# cloud_sensor.net
KiCad netlist of a schematic drawn in EAGLE
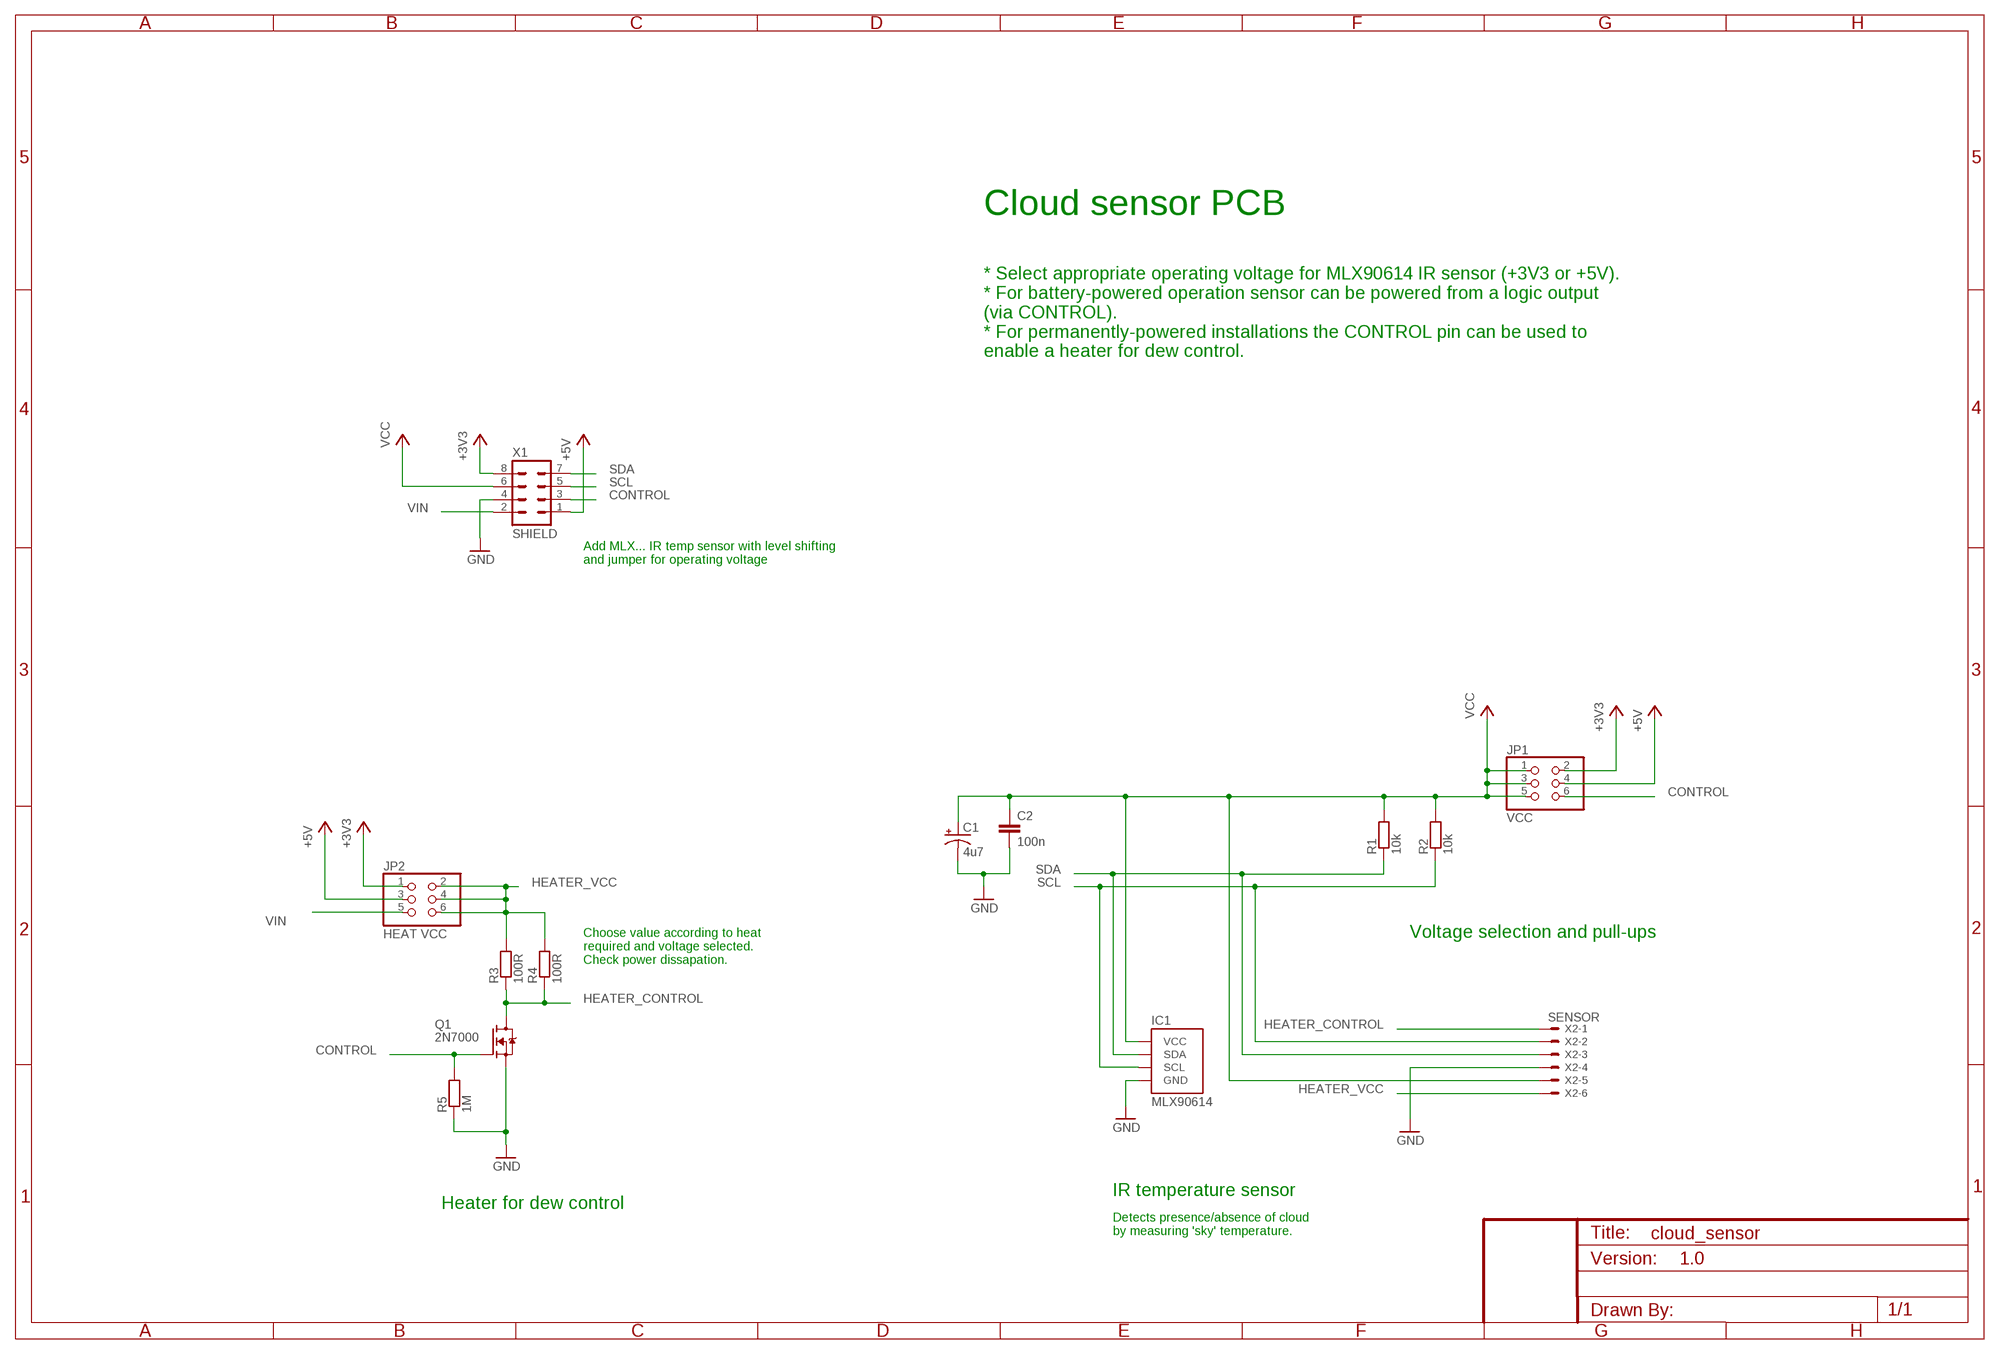
[diagram p0: schematic, sheet 1]

(export (version "E")
  (design (tool "Eeschema 10.0.6"))
  (components
    (comp (ref "C1")
      (value "4u7")
      (footprint "eagle-import:CPOL-RADIAL-10UF-25V")
      (libsource (lib "eagle-import") (part "CAP_POLPTH2"))
    )
    (comp (ref "C2")
      (value "100n")
      (footprint "eagle-import:CAP-PTH-SMALL")
      (libsource (lib "eagle-import") (part "CAPPTH"))
    )
    (comp (ref "IC1")
      (value "MLX90614")
      (footprint "eagle-import:TO39-4")
      (libsource (lib "eagle-import") (part "MLX90614TO-39"))
    )
    (comp (ref "JP1")
      (value "VCC")
      (footprint "eagle-import:2X03")
      (libsource (lib "eagle-import") (part "PINHD-2X3"))
    )
    (comp (ref "JP2")
      (value "HEAT VCC")
      (footprint "eagle-import:2X03")
      (libsource (lib "eagle-import") (part "PINHD-2X3"))
    )
    (comp (ref "Q1")
      (value "2N7000")
      (footprint "eagle-import:TO-92")
      (libsource (lib "eagle-import") (part "2N7000"))
    )
    (comp (ref "R1")
      (value "10k")
      (footprint "eagle-import:RES-AXIAL-0.4")
      (libsource (lib "eagle-import") (part "RESISTOR"))
    )
    (comp (ref "R2")
      (value "10k")
      (footprint "eagle-import:RES-AXIAL-0.4")
      (libsource (lib "eagle-import") (part "RESISTOR"))
    )
    (comp (ref "R3")
      (value "100R")
      (footprint "eagle-import:RES-AXIAL-0.4")
      (libsource (lib "eagle-import") (part "RESISTOR"))
    )
    (comp (ref "R4")
      (value "100R")
      (footprint "eagle-import:RES-AXIAL-0.4")
      (libsource (lib "eagle-import") (part "RESISTOR"))
    )
    (comp (ref "R5")
      (value "1M")
      (footprint "eagle-import:RES-AXIAL-0.4")
      (libsource (lib "eagle-import") (part "RESISTOR"))
    )
    (comp (ref "X1")
      (value "SHIELD")
      (footprint "eagle-import:ML8")
      (libsource (lib "eagle-import") (part "ML8"))
    )
    (comp (ref "X2")
      (value "SENSOR")
      (footprint "eagle-import:22-23-2061")
      (fields (field (name "MF") "MOLEX") (field (name "MPN") "22-23-2061"))
      (libsource (lib "eagle-import") (part "22-23-2061"))
    )
  )
  (nets
    (net (code "1") (name "+3V3") (class "Default")
      (node (ref "JP1") (pin "2") (pinfunction "2_2") (pintype "passive"))
      (node (ref "JP2") (pin "1") (pinfunction "1_1") (pintype "passive"))
      (node (ref "X1") (pin "8") (pinfunction "8_8") (pintype "passive"))
    )
    (net (code "2") (name "+5V") (class "Default")
      (node (ref "JP1") (pin "4") (pinfunction "4_4") (pintype "passive"))
      (node (ref "JP2") (pin "3") (pinfunction "3_3") (pintype "passive"))
      (node (ref "X1") (pin "1") (pinfunction "1_1") (pintype "passive"))
    )
    (net (code "3") (name "/CONTROL") (class "Default")
      (node (ref "JP1") (pin "6") (pinfunction "6_6") (pintype "passive"))
      (node (ref "Q1") (pin "2") (pinfunction "G_2") (pintype "passive"))
      (node (ref "R5") (pin "P$2") (pinfunction "2_P$2") (pintype "passive"))
      (node (ref "X1") (pin "3") (pinfunction "3_3") (pintype "passive"))
    )
    (net (code "4") (name "/HEATER_CONTROL") (class "Default")
      (node (ref "Q1") (pin "3") (pinfunction "D_3") (pintype "passive"))
      (node (ref "R3") (pin "P$1") (pinfunction "1_P$1") (pintype "passive"))
      (node (ref "R4") (pin "P$1") (pinfunction "1_P$1") (pintype "passive"))
      (node (ref "X2") (pin "1") (pinfunction "S_1") (pintype "passive"))
    )
    (net (code "5") (name "/HEATER_VCC") (class "Default")
      (node (ref "JP2") (pin "2") (pinfunction "2_2") (pintype "passive"))
      (node (ref "JP2") (pin "4") (pinfunction "4_4") (pintype "passive"))
      (node (ref "JP2") (pin "6") (pinfunction "6_6") (pintype "passive"))
      (node (ref "R3") (pin "P$2") (pinfunction "2_P$2") (pintype "passive"))
      (node (ref "R4") (pin "P$2") (pinfunction "2_P$2") (pintype "passive"))
      (node (ref "X2") (pin "6") (pinfunction "S_6") (pintype "passive"))
    )
    (net (code "6") (name "/SCL") (class "Default")
      (node (ref "IC1") (pin "1") (pinfunction "SCL_1") (pintype "bidirectional"))
      (node (ref "R2") (pin "P$1") (pinfunction "1_P$1") (pintype "passive"))
      (node (ref "X1") (pin "5") (pinfunction "5_5") (pintype "passive"))
      (node (ref "X2") (pin "2") (pinfunction "S_2") (pintype "passive"))
    )
    (net (code "7") (name "/SDA") (class "Default")
      (node (ref "IC1") (pin "2") (pinfunction "SDA_2") (pintype "bidirectional"))
      (node (ref "R1") (pin "P$1") (pinfunction "1_P$1") (pintype "passive"))
      (node (ref "X1") (pin "7") (pinfunction "7_7") (pintype "passive"))
      (node (ref "X2") (pin "3") (pinfunction "S_3") (pintype "passive"))
    )
    (net (code "8") (name "/VIN") (class "Default")
      (node (ref "JP2") (pin "5") (pinfunction "5_5") (pintype "passive"))
      (node (ref "X1") (pin "2") (pinfunction "2_2") (pintype "passive"))
    )
    (net (code "9") (name "GND") (class "Default")
      (node (ref "C1") (pin "2") (pinfunction "-_2") (pintype "passive"))
      (node (ref "C2") (pin "2") (pinfunction "2_2") (pintype "passive"))
      (node (ref "IC1") (pin "4") (pinfunction "GND_4") (pintype "power_in"))
      (node (ref "Q1") (pin "1") (pinfunction "S_1") (pintype "passive"))
      (node (ref "R5") (pin "P$1") (pinfunction "1_P$1") (pintype "passive"))
      (node (ref "X1") (pin "4") (pinfunction "4_4") (pintype "passive"))
      (node (ref "X2") (pin "4") (pinfunction "S_4") (pintype "passive"))
    )
    (net (code "10") (name "VCC") (class "Default")
      (node (ref "C1") (pin "1") (pinfunction "+_1") (pintype "passive"))
      (node (ref "C2") (pin "1") (pinfunction "1_1") (pintype "passive"))
      (node (ref "IC1") (pin "3") (pinfunction "VCC_3") (pintype "power_in"))
      (node (ref "JP1") (pin "1") (pinfunction "1_1") (pintype "passive"))
      (node (ref "JP1") (pin "3") (pinfunction "3_3") (pintype "passive"))
      (node (ref "JP1") (pin "5") (pinfunction "5_5") (pintype "passive"))
      (node (ref "R1") (pin "P$2") (pinfunction "2_P$2") (pintype "passive"))
      (node (ref "R2") (pin "P$2") (pinfunction "2_P$2") (pintype "passive"))
      (node (ref "X1") (pin "6") (pinfunction "6_6") (pintype "passive"))
      (node (ref "X2") (pin "5") (pinfunction "S_5") (pintype "passive"))
    )
  )
)
